# zero_board.net
KiCad netlist of a schematic drawn in EAGLE
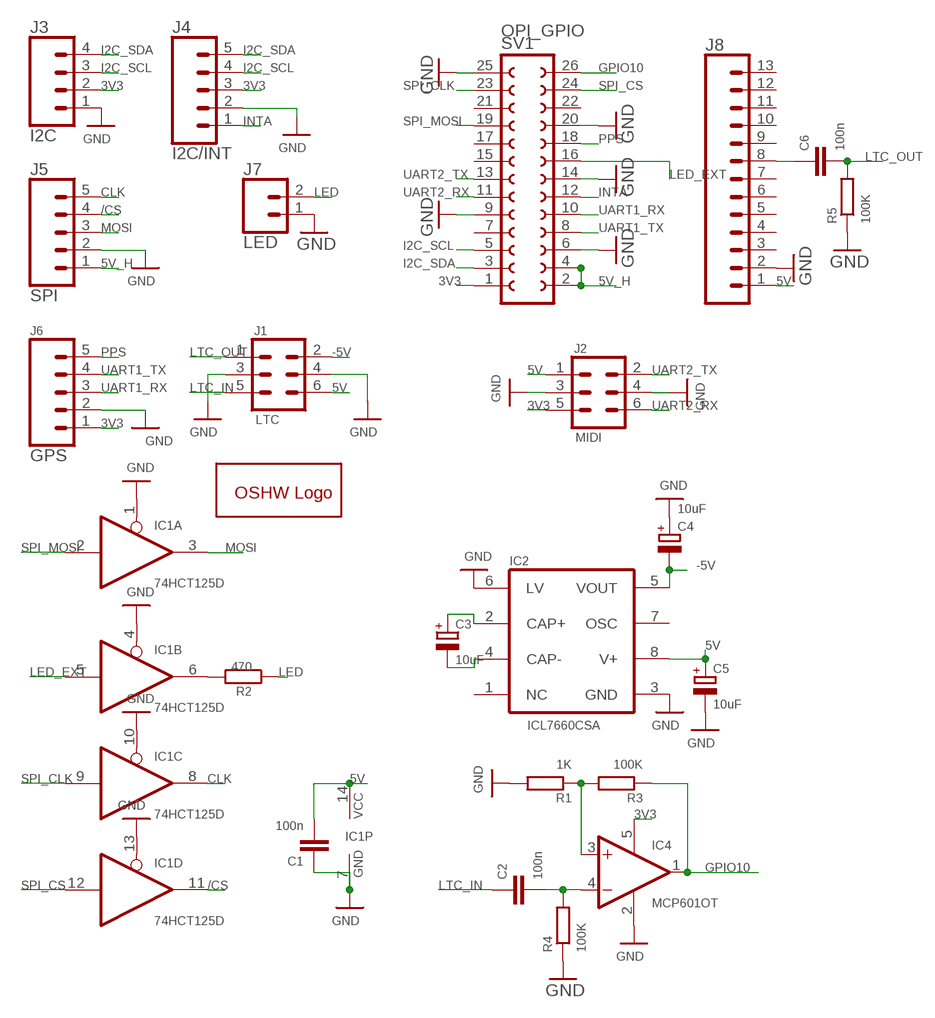
[diagram p0: schematic, sheet 1]

(export (version "E")
  (design (tool "Eeschema 10.0.6"))
  (components
    (comp (ref "C1")
      (value "100n")
      (footprint "eagle-import:C0603")
      (libsource (lib "eagle-import") (part "C-EUC0603"))
    )
    (comp (ref "C2")
      (value "100n")
      (footprint "eagle-import:C0603")
      (libsource (lib "eagle-import") (part "C-EUC0603"))
    )
    (comp (ref "C3")
      (value "10uF")
      (footprint "eagle-import:153CLV-0405")
      (libsource (lib "eagle-import") (part "CPOL-EU153CLV-0405"))
    )
    (comp (ref "C4")
      (value "10uF")
      (footprint "eagle-import:153CLV-0405")
      (libsource (lib "eagle-import") (part "CPOL-EU153CLV-0405"))
    )
    (comp (ref "C5")
      (value "10uF")
      (footprint "eagle-import:153CLV-0405")
      (libsource (lib "eagle-import") (part "CPOL-EU153CLV-0405"))
    )
    (comp (ref "C6")
      (value "100n")
      (footprint "eagle-import:C0603")
      (libsource (lib "eagle-import") (part "C-EUC0603"))
    )
    (comp (ref "GOLD_ORB_SM1")
      (value "OSHWLOGOLOGO5MM")
      (footprint "eagle-import:OSHW_5MM")
      (libsource (lib "eagle-import") (part "OSHWLOGOLOGO5MM"))
    )
    (comp (ref "IC1")
      (value "74HCT125D")
      (footprint "eagle-import:SO14")
      (libsource (lib "eagle-import") (part "74125DHCT"))
    )
    (comp (ref "IC2")
      (value "ICL7660CSA")
      (footprint "eagle-import:SO08")
      (fields (field (name "MF") "MAXIM"))
      (libsource (lib "eagle-import") (part "ICL7660CSA"))
    )
    (comp (ref "IC4")
      (value "MCP601OT")
      (footprint "eagle-import:SOT23-5")
      (libsource (lib "eagle-import") (part "MCP601OT"))
    )
    (comp (ref "J1")
      (value "LTC")
      (footprint "eagle-import:2X3")
      (libsource (lib "eagle-import") (part "SparkFun-Connectors_513_CONN_03X22X3_SILK_MALE_PTH"))
    )
    (comp (ref "J2")
      (value "MIDI")
      (footprint "eagle-import:2X3-SHROUDED")
      (libsource (lib "eagle-import") (part "CONN_03X2SHROUD"))
    )
    (comp (ref "J3")
      (value "I2C")
      (footprint "eagle-import:1X04")
      (libsource (lib "eagle-import") (part "CONN_04"))
    )
    (comp (ref "J4")
      (value "I2C/INT")
      (footprint "eagle-import:1X05")
      (libsource (lib "eagle-import") (part "CONN_05"))
    )
    (comp (ref "J5")
      (value "SPI")
      (footprint "eagle-import:1X05")
      (libsource (lib "eagle-import") (part "CONN_05"))
    )
    (comp (ref "J6")
      (value "GPS")
      (footprint "eagle-import:1X05")
      (libsource (lib "eagle-import") (part "CONN_05"))
    )
    (comp (ref "J7")
      (value "LED")
      (footprint "eagle-import:1X02")
      (libsource (lib "eagle-import") (part "CONN_02"))
    )
    (comp (ref "J8")
      (value "CONN_13")
      (footprint "eagle-import:1X13")
      (libsource (lib "eagle-import") (part "CONN_13"))
    )
    (comp (ref "R1")
      (value "1K")
      (footprint "eagle-import:R0603")
      (libsource (lib "eagle-import") (part "R-EU_R0603"))
    )
    (comp (ref "R2")
      (value "470")
      (footprint "eagle-import:R0603")
      (libsource (lib "eagle-import") (part "R-EU_R0603"))
    )
    (comp (ref "R3")
      (value "100K")
      (footprint "eagle-import:R0603")
      (libsource (lib "eagle-import") (part "R-EU_R0603"))
    )
    (comp (ref "R4")
      (value "100K")
      (footprint "eagle-import:R0603")
      (libsource (lib "eagle-import") (part "R-EU_R0603"))
    )
    (comp (ref "R5")
      (value "100K")
      (footprint "eagle-import:R0603")
      (libsource (lib "eagle-import") (part "R-EU_R0603"))
    )
    (comp (ref "SV1")
      (value "OPI_GPIO")
      (footprint "eagle-import:FE13-2")
      (libsource (lib "eagle-import") (part "FE13-2"))
    )
  )
  (nets
    (net (code "1") (name "/-5V") (class "Default")
      (node (ref "C4") (pin "-") (pinfunction "-_-") (pintype "passive"))
      (node (ref "IC2") (pin "5") (pinfunction "VOUT_5") (pintype "output"))
      (node (ref "J1") (pin "2") (pinfunction "2_2") (pintype "bidirectional"))
    )
    (net (code "2") (name "/3V3") (class "Default")
      (node (ref "IC4") (pin "5") (pinfunction "V+_5") (pintype "power_in"))
      (node (ref "J2") (pin "5") (pinfunction "5_5") (pintype "bidirectional"))
      (node (ref "J3") (pin "2") (pinfunction "2_2") (pintype "passive"))
      (node (ref "J4") (pin "3") (pinfunction "3_3") (pintype "passive"))
      (node (ref "J6") (pin "1") (pinfunction "1_1") (pintype "passive"))
      (node (ref "SV1") (pin "1") (pinfunction "1_1") (pintype "passive"))
    )
    (net (code "3") (name "/5V") (class "Default")
      (node (ref "C1") (pin "2") (pinfunction "2_2") (pintype "passive"))
      (node (ref "C5") (pin "+") (pinfunction "+_+") (pintype "passive"))
      (node (ref "IC1") (pin "14") (pinfunction "VCC_14") (pintype "power_in"))
      (node (ref "IC2") (pin "8") (pinfunction "V+_8") (pintype "power_in"))
      (node (ref "J1") (pin "6") (pinfunction "6_6") (pintype "bidirectional"))
      (node (ref "J2") (pin "1") (pinfunction "1_1") (pintype "bidirectional"))
      (node (ref "J8") (pin "1") (pinfunction "1_1") (pintype "passive"))
    )
    (net (code "4") (name "/5V_H") (class "Default")
      (node (ref "J5") (pin "1") (pinfunction "1_1") (pintype "passive"))
      (node (ref "SV1") (pin "2") (pinfunction "2_2") (pintype "passive"))
      (node (ref "SV1") (pin "4") (pinfunction "4_4") (pintype "passive"))
    )
    (net (code "5") (name "/CLK") (class "Default")
      (node (ref "IC1") (pin "8") (pinfunction "O_8") (pintype "tri_state"))
      (node (ref "J5") (pin "5") (pinfunction "5_5") (pintype "passive"))
    )
    (net (code "6") (name "/GPIO10") (class "Default")
      (node (ref "IC4") (pin "1") (pinfunction "OUT_1") (pintype "output"))
      (node (ref "R3") (pin "1") (pinfunction "1_1") (pintype "passive"))
      (node (ref "SV1") (pin "26") (pinfunction "26_26") (pintype "passive"))
    )
    (net (code "7") (name "/I2C_SCL") (class "Default")
      (node (ref "J3") (pin "3") (pinfunction "3_3") (pintype "passive"))
      (node (ref "J4") (pin "4") (pinfunction "4_4") (pintype "passive"))
      (node (ref "SV1") (pin "5") (pinfunction "5_5") (pintype "passive"))
    )
    (net (code "8") (name "/I2C_SDA") (class "Default")
      (node (ref "J3") (pin "4") (pinfunction "4_4") (pintype "passive"))
      (node (ref "J4") (pin "5") (pinfunction "5_5") (pintype "passive"))
      (node (ref "SV1") (pin "3") (pinfunction "3_3") (pintype "passive"))
    )
    (net (code "9") (name "/INTA") (class "Default")
      (node (ref "J4") (pin "1") (pinfunction "1_1") (pintype "passive"))
      (node (ref "SV1") (pin "12") (pinfunction "12_12") (pintype "passive"))
    )
    (net (code "10") (name "/LED") (class "Default")
      (node (ref "J7") (pin "2") (pinfunction "2_2") (pintype "passive"))
      (node (ref "R2") (pin "1") (pinfunction "1_1") (pintype "passive"))
    )
    (net (code "11") (name "/LED_EXT") (class "Default")
      (node (ref "IC1") (pin "5") (pinfunction "I_5") (pintype "input"))
      (node (ref "SV1") (pin "16") (pinfunction "16_16") (pintype "passive"))
    )
    (net (code "12") (name "/LTC_IN") (class "Default")
      (node (ref "C2") (pin "1") (pinfunction "1_1") (pintype "passive"))
      (node (ref "J1") (pin "5") (pinfunction "5_5") (pintype "bidirectional"))
    )
    (net (code "13") (name "/LTC_OUT") (class "Default")
      (node (ref "C6") (pin "2") (pinfunction "2_2") (pintype "passive"))
      (node (ref "J1") (pin "1") (pinfunction "1_1") (pintype "bidirectional"))
      (node (ref "R5") (pin "2") (pinfunction "2_2") (pintype "passive"))
    )
    (net (code "14") (name "/MOSI") (class "Default")
      (node (ref "IC1") (pin "3") (pinfunction "O_3") (pintype "tri_state"))
      (node (ref "J5") (pin "3") (pinfunction "3_3") (pintype "passive"))
    )
    (net (code "15") (name "/PPS") (class "Default")
      (node (ref "J6") (pin "5") (pinfunction "5_5") (pintype "passive"))
      (node (ref "SV1") (pin "18") (pinfunction "18_18") (pintype "passive"))
    )
    (net (code "16") (name "/SPI_CLK") (class "Default")
      (node (ref "IC1") (pin "9") (pinfunction "I_9") (pintype "input"))
      (node (ref "SV1") (pin "23") (pinfunction "23_23") (pintype "passive"))
    )
    (net (code "17") (name "/SPI_CS") (class "Default")
      (node (ref "IC1") (pin "12") (pinfunction "I_12") (pintype "input"))
      (node (ref "SV1") (pin "24") (pinfunction "24_24") (pintype "passive"))
    )
    (net (code "18") (name "/SPI_MOSI") (class "Default")
      (node (ref "IC1") (pin "2") (pinfunction "I_2") (pintype "input"))
      (node (ref "SV1") (pin "19") (pinfunction "19_19") (pintype "passive"))
    )
    (net (code "19") (name "/UART1_RX") (class "Default")
      (node (ref "J6") (pin "3") (pinfunction "3_3") (pintype "passive"))
      (node (ref "SV1") (pin "10") (pinfunction "10_10") (pintype "passive"))
    )
    (net (code "20") (name "/UART1_TX") (class "Default")
      (node (ref "J6") (pin "4") (pinfunction "4_4") (pintype "passive"))
      (node (ref "SV1") (pin "8") (pinfunction "8_8") (pintype "passive"))
    )
    (net (code "21") (name "/UART2_RX") (class "Default")
      (node (ref "J2") (pin "6") (pinfunction "6_6") (pintype "bidirectional"))
      (node (ref "SV1") (pin "11") (pinfunction "11_11") (pintype "passive"))
    )
    (net (code "22") (name "/UART2_TX") (class "Default")
      (node (ref "J2") (pin "2") (pinfunction "2_2") (pintype "bidirectional"))
      (node (ref "SV1") (pin "13") (pinfunction "13_13") (pintype "passive"))
    )
    (net (code "23") (name "/{slash}CS") (class "Default")
      (node (ref "IC1") (pin "11") (pinfunction "O_11") (pintype "tri_state"))
      (node (ref "J5") (pin "4") (pinfunction "4_4") (pintype "passive"))
    )
    (net (code "24") (name "GND") (class "Default")
      (node (ref "C1") (pin "1") (pinfunction "1_1") (pintype "passive"))
      (node (ref "C4") (pin "+") (pinfunction "+_+") (pintype "passive"))
      (node (ref "C5") (pin "-") (pinfunction "-_-") (pintype "passive"))
      (node (ref "IC1") (pin "1") (pinfunction "OE_1") (pintype "input"))
      (node (ref "IC1") (pin "10") (pinfunction "OE_10") (pintype "input"))
      (node (ref "IC1") (pin "13") (pinfunction "OE_13") (pintype "input"))
      (node (ref "IC1") (pin "4") (pinfunction "OE_4") (pintype "input"))
      (node (ref "IC1") (pin "7") (pinfunction "GND_7") (pintype "power_in"))
      (node (ref "IC2") (pin "3") (pinfunction "GND_3") (pintype "power_in"))
      (node (ref "IC2") (pin "6") (pinfunction "LV_6") (pintype "passive"))
      (node (ref "IC4") (pin "2") (pinfunction "V-_2") (pintype "power_in"))
      (node (ref "J1") (pin "3") (pinfunction "3_3") (pintype "bidirectional"))
      (node (ref "J1") (pin "4") (pinfunction "4_4") (pintype "bidirectional"))
      (node (ref "J2") (pin "3") (pinfunction "3_3") (pintype "bidirectional"))
      (node (ref "J2") (pin "4") (pinfunction "4_4") (pintype "bidirectional"))
      (node (ref "J3") (pin "1") (pinfunction "1_1") (pintype "passive"))
      (node (ref "J4") (pin "2") (pinfunction "2_2") (pintype "passive"))
      (node (ref "J5") (pin "2") (pinfunction "2_2") (pintype "passive"))
      (node (ref "J6") (pin "2") (pinfunction "2_2") (pintype "passive"))
      (node (ref "J7") (pin "1") (pinfunction "1_1") (pintype "passive"))
      (node (ref "J8") (pin "2") (pinfunction "2_2") (pintype "passive"))
      (node (ref "R1") (pin "2") (pinfunction "2_2") (pintype "passive"))
      (node (ref "R4") (pin "1") (pinfunction "1_1") (pintype "passive"))
      (node (ref "R5") (pin "1") (pinfunction "1_1") (pintype "passive"))
      (node (ref "SV1") (pin "14") (pinfunction "14_14") (pintype "passive"))
      (node (ref "SV1") (pin "20") (pinfunction "20_20") (pintype "passive"))
      (node (ref "SV1") (pin "25") (pinfunction "25_25") (pintype "passive"))
      (node (ref "SV1") (pin "6") (pinfunction "6_6") (pintype "passive"))
      (node (ref "SV1") (pin "9") (pinfunction "9_9") (pintype "passive"))
    )
    (net (code "25") (name "Net-(C6-Pad1)") (class "Default")
      (node (ref "C6") (pin "1") (pinfunction "1_1") (pintype "passive"))
      (node (ref "J8") (pin "8") (pinfunction "8_8") (pintype "passive"))
    )
    (net (code "26") (name "Net-(IC1B-O)") (class "Default")
      (node (ref "IC1") (pin "6") (pinfunction "O_6") (pintype "tri_state"))
      (node (ref "R2") (pin "2") (pinfunction "2_2") (pintype "passive"))
    )
    (net (code "27") (name "Net-(IC2-CAP+)") (class "Default")
      (node (ref "C3") (pin "+") (pinfunction "+_+") (pintype "passive"))
      (node (ref "IC2") (pin "2") (pinfunction "CAP+_2") (pintype "passive"))
    )
    (net (code "28") (name "Net-(IC2-CAP-)") (class "Default")
      (node (ref "C3") (pin "-") (pinfunction "-_-") (pintype "passive"))
      (node (ref "IC2") (pin "4") (pinfunction "CAP-_4") (pintype "passive"))
    )
    (net (code "29") (name "Net-(IC4-+IN)") (class "Default")
      (node (ref "IC4") (pin "3") (pinfunction "+IN_3") (pintype "input"))
      (node (ref "R1") (pin "1") (pinfunction "1_1") (pintype "passive"))
      (node (ref "R3") (pin "2") (pinfunction "2_2") (pintype "passive"))
    )
    (net (code "30") (name "Net-(IC4--IN)") (class "Default")
      (node (ref "C2") (pin "2") (pinfunction "2_2") (pintype "passive"))
      (node (ref "IC4") (pin "4") (pinfunction "-IN_4") (pintype "input"))
      (node (ref "R4") (pin "2") (pinfunction "2_2") (pintype "passive"))
    )
    (net (code "31") (name "unconnected-(IC2-NC-Pad1)") (class "Default")
      (node (ref "IC2") (pin "1") (pinfunction "NC_1") (pintype "no_connect"))
    )
    (net (code "32") (name "unconnected-(IC2-OSC-Pad7)") (class "Default")
      (node (ref "IC2") (pin "7") (pinfunction "OSC_7") (pintype "output"))
    )
    (net (code "33") (name "unconnected-(J8-Pad3)") (class "Default")
      (node (ref "J8") (pin "3") (pinfunction "3_3") (pintype "passive"))
    )
    (net (code "34") (name "unconnected-(J8-Pad4)") (class "Default")
      (node (ref "J8") (pin "4") (pinfunction "4_4") (pintype "passive"))
    )
    (net (code "35") (name "unconnected-(J8-Pad5)") (class "Default")
      (node (ref "J8") (pin "5") (pinfunction "5_5") (pintype "passive"))
    )
    (net (code "36") (name "unconnected-(J8-Pad6)") (class "Default")
      (node (ref "J8") (pin "6") (pinfunction "6_6") (pintype "passive"))
    )
    (net (code "37") (name "unconnected-(J8-Pad7)") (class "Default")
      (node (ref "J8") (pin "7") (pinfunction "7_7") (pintype "passive"))
    )
    (net (code "38") (name "unconnected-(J8-Pad9)") (class "Default")
      (node (ref "J8") (pin "9") (pinfunction "9_9") (pintype "passive"))
    )
    (net (code "39") (name "unconnected-(J8-Pad10)") (class "Default")
      (node (ref "J8") (pin "10") (pinfunction "10_10") (pintype "passive"))
    )
    (net (code "40") (name "unconnected-(J8-Pad11)") (class "Default")
      (node (ref "J8") (pin "11") (pinfunction "11_11") (pintype "passive"))
    )
    (net (code "41") (name "unconnected-(J8-Pad12)") (class "Default")
      (node (ref "J8") (pin "12") (pinfunction "12_12") (pintype "passive"))
    )
    (net (code "42") (name "unconnected-(J8-Pad13)") (class "Default")
      (node (ref "J8") (pin "13") (pinfunction "13_13") (pintype "passive"))
    )
    (net (code "43") (name "unconnected-(SV1-Pad7)") (class "Default")
      (node (ref "SV1") (pin "7") (pinfunction "7_7") (pintype "passive"))
    )
    (net (code "44") (name "unconnected-(SV1-Pad15)") (class "Default")
      (node (ref "SV1") (pin "15") (pinfunction "15_15") (pintype "passive"))
    )
    (net (code "45") (name "unconnected-(SV1-Pad17)") (class "Default")
      (node (ref "SV1") (pin "17") (pinfunction "17_17") (pintype "passive"))
    )
    (net (code "46") (name "unconnected-(SV1-Pad21)") (class "Default")
      (node (ref "SV1") (pin "21") (pinfunction "21_21") (pintype "passive"))
    )
    (net (code "47") (name "unconnected-(SV1-Pad22)") (class "Default")
      (node (ref "SV1") (pin "22") (pinfunction "22_22") (pintype "passive"))
    )
  )
)
